# fanmon.net
KiCad netlist of a schematic drawn in EAGLE
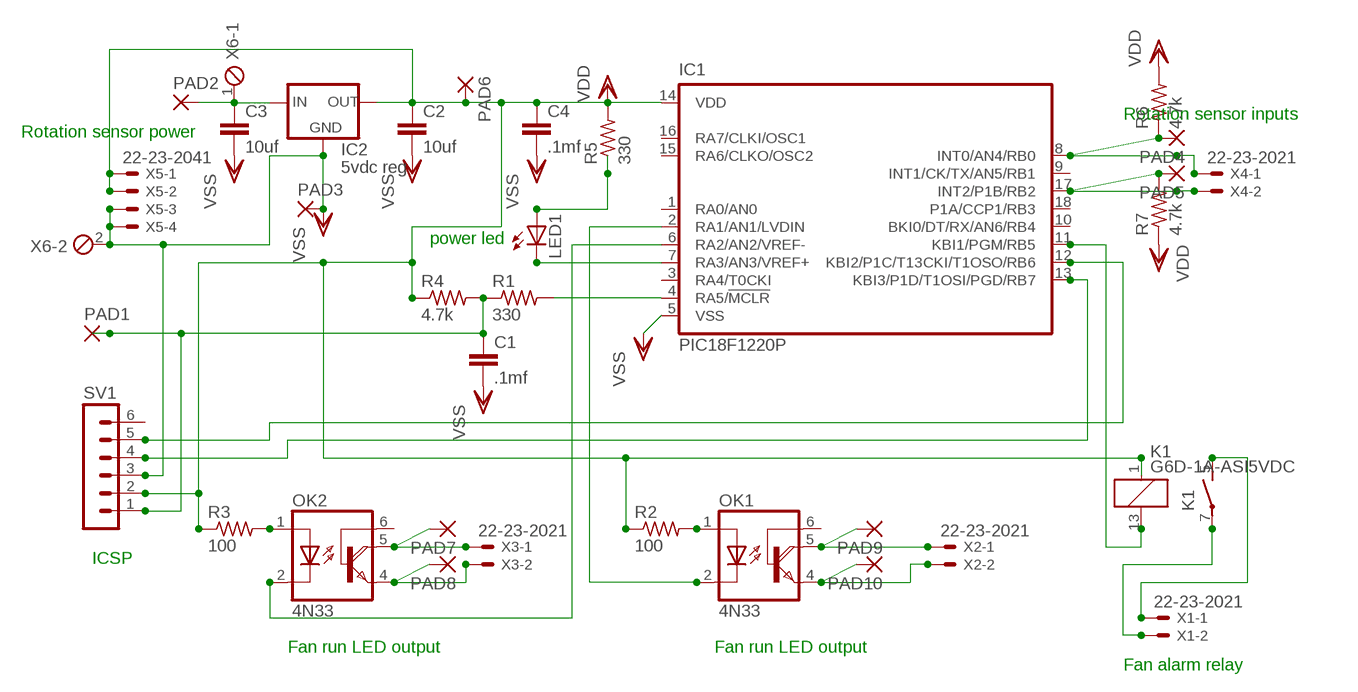
[diagram p0: schematic, sheet 1]

(export (version "E")
  (design (tool "Eeschema 10.0.6"))
  (components
    (comp (ref "C1")
      (value ".1mf")
      (footprint "eagle-import:C5B2.5")
      (libsource (lib "eagle-import") (part "C5/2.5"))
    )
    (comp (ref "C2")
      (value "10uf")
      (footprint "eagle-import:C5B2.5")
      (libsource (lib "eagle-import") (part "C5/2.5"))
    )
    (comp (ref "C3")
      (value "10uf")
      (footprint "eagle-import:C5B2.5")
      (libsource (lib "eagle-import") (part "C5/2.5"))
    )
    (comp (ref "C4")
      (value ".1mf")
      (footprint "eagle-import:C5B2.5")
      (libsource (lib "eagle-import") (part "C5/2.5"))
    )
    (comp (ref "IC1")
      (value "PIC18F1220P")
      (footprint "eagle-import:DIL18")
      (fields (field (name "MF") "MICROCHIP") (field (name "MPN") "PIC18F1220-I/P"))
      (libsource (lib "eagle-import") (part "PIC18F120P2"))
    )
    (comp (ref "IC2")
      (value "5vdc reg")
      (footprint "eagle-import:78XXL")
      (libsource (lib "eagle-import") (part "78XXL"))
    )
    (comp (ref "K1")
      (value "G6D-1A-ASI5VDC")
      (footprint "eagle-import:G6D")
      (libsource (lib "eagle-import") (part "G6D?-1A-ASI5VDC"))
    )
    (comp (ref "LED1")
      (value "LED5MM")
      (footprint "eagle-import:LED5MM")
      (libsource (lib "eagle-import") (part "LED5MM"))
    )
    (comp (ref "OK1")
      (value "4N33")
      (footprint "eagle-import:DIL06")
      (fields (field (name "MF") "VISHAY/TELEFUNKEN"))
      (libsource (lib "eagle-import") (part "4N33"))
    )
    (comp (ref "OK2")
      (value "4N33")
      (footprint "eagle-import:DIL06")
      (fields (field (name "MF") "VISHAY/TELEFUNKEN"))
      (libsource (lib "eagle-import") (part "4N33"))
    )
    (comp (ref "PAD1")
      (value "1,6/0,8")
      (footprint "eagle-import:1,6_0,8")
      (libsource (lib "eagle-import") (part "1,6/0,8"))
    )
    (comp (ref "PAD2")
      (value "1,6/0,8")
      (footprint "eagle-import:1,6_0,8")
      (libsource (lib "eagle-import") (part "1,6/0,8"))
    )
    (comp (ref "PAD3")
      (value "1,6/0,8")
      (footprint "eagle-import:1,6_0,8")
      (libsource (lib "eagle-import") (part "1,6/0,8"))
    )
    (comp (ref "PAD4")
      (value "1,6/0,8")
      (footprint "eagle-import:1,6_0,8")
      (libsource (lib "eagle-import") (part "1,6/0,8"))
    )
    (comp (ref "PAD5")
      (value "1,6/0,8")
      (footprint "eagle-import:1,6_0,8")
      (libsource (lib "eagle-import") (part "1,6/0,8"))
    )
    (comp (ref "PAD6")
      (value "1,6/0,8")
      (footprint "eagle-import:1,6_0,8")
      (libsource (lib "eagle-import") (part "1,6/0,8"))
    )
    (comp (ref "PAD7")
      (value "1,6/0,8")
      (footprint "eagle-import:1,6_0,8")
      (libsource (lib "eagle-import") (part "1,6/0,8"))
    )
    (comp (ref "PAD8")
      (value "1,6/0,8")
      (footprint "eagle-import:1,6_0,8")
      (libsource (lib "eagle-import") (part "1,6/0,8"))
    )
    (comp (ref "PAD9")
      (value "1,6/0,8")
      (footprint "eagle-import:1,6_0,8")
      (libsource (lib "eagle-import") (part "1,6/0,8"))
    )
    (comp (ref "PAD10")
      (value "1,6/0,8")
      (footprint "eagle-import:1,6_0,8")
      (libsource (lib "eagle-import") (part "1,6/0,8"))
    )
    (comp (ref "R1")
      (value "330")
      (footprint "eagle-import:0204V")
      (libsource (lib "eagle-import") (part "R-US_0204/2V"))
    )
    (comp (ref "R2")
      (value "100")
      (footprint "eagle-import:0204V")
      (libsource (lib "eagle-import") (part "R-US_0204/2V"))
    )
    (comp (ref "R3")
      (value "100")
      (footprint "eagle-import:0204V")
      (libsource (lib "eagle-import") (part "R-US_0204/2V"))
    )
    (comp (ref "R4")
      (value "4.7k")
      (footprint "eagle-import:0204V")
      (libsource (lib "eagle-import") (part "R-US_0204/2V"))
    )
    (comp (ref "R5")
      (value "330")
      (footprint "eagle-import:0204V")
      (libsource (lib "eagle-import") (part "R-US_0204/2V"))
    )
    (comp (ref "R6")
      (value "4.7k")
      (footprint "eagle-import:0204V")
      (libsource (lib "eagle-import") (part "R-US_0204/2V"))
    )
    (comp (ref "R7")
      (value "4.7k")
      (footprint "eagle-import:0204V")
      (libsource (lib "eagle-import") (part "R-US_0204/2V"))
    )
    (comp (ref "SV1")
      (value "MA06-1")
      (footprint "eagle-import:MA06-1")
      (libsource (lib "eagle-import") (part "MA06-1"))
    )
    (comp (ref "X1")
      (value "22-23-2021")
      (footprint "eagle-import:22-23-2021")
      (fields (field (name "MF") "MOLEX"))
      (libsource (lib "eagle-import") (part "22-23-2021"))
    )
    (comp (ref "X2")
      (value "22-23-2021")
      (footprint "eagle-import:22-23-2021")
      (fields (field (name "MF") "MOLEX"))
      (libsource (lib "eagle-import") (part "22-23-2021"))
    )
    (comp (ref "X3")
      (value "22-23-2021")
      (footprint "eagle-import:22-23-2021")
      (fields (field (name "MF") "MOLEX"))
      (libsource (lib "eagle-import") (part "22-23-2021"))
    )
    (comp (ref "X4")
      (value "22-23-2021")
      (footprint "eagle-import:22-23-2021")
      (fields (field (name "MF") "MOLEX"))
      (libsource (lib "eagle-import") (part "22-23-2021"))
    )
    (comp (ref "X5")
      (value "22-23-2041")
      (footprint "eagle-import:22-23-2041")
      (fields (field (name "MF") "MOLEX"))
      (libsource (lib "eagle-import") (part "22-23-2041"))
    )
    (comp (ref "X6")
      (value "MPT2")
      (footprint "eagle-import:2POL254")
      (libsource (lib "eagle-import") (part "MPT2"))
    )
  )
  (nets
    (net (code "1") (name "Net-(IC1-INT0{slash}AN4{slash}RB0)") (class "Default")
      (node (ref "IC1") (pin "8") (pinfunction "INT0/AN4/RB0_8") (pintype "bidirectional"))
      (node (ref "PAD4") (pin "1") (pinfunction "P_1") (pintype "passive"))
      (node (ref "R6") (pin "1") (pinfunction "1_1") (pintype "passive"))
      (node (ref "X4") (pin "1") (pinfunction "S_1") (pintype "passive"))
    )
    (net (code "2") (name "Net-(IC1-INT2{slash}P1B{slash}RB2)") (class "Default")
      (node (ref "IC1") (pin "17") (pinfunction "INT2/P1B/RB2_17") (pintype "bidirectional"))
      (node (ref "PAD5") (pin "1") (pinfunction "P_1") (pintype "passive"))
      (node (ref "R7") (pin "2") (pinfunction "2_2") (pintype "passive"))
      (node (ref "X4") (pin "2") (pinfunction "S_2") (pintype "passive"))
    )
    (net (code "3") (name "Net-(IC1-KBI1{slash}PGM{slash}RB5)") (class "Default")
      (node (ref "IC1") (pin "11") (pinfunction "KBI1/PGM/RB5_11") (pintype "bidirectional"))
      (node (ref "K1") (pin "13") (pinfunction "2_13") (pintype "passive"))
    )
    (net (code "4") (name "Net-(IC1-KBI2{slash}P1C{slash}T13CKI{slash}T1OSO{slash}RB6)") (class "Default")
      (node (ref "IC1") (pin "12") (pinfunction "KBI2/P1C/T13CKI/T1OSO/RB6_12") (pintype "bidirectional"))
      (node (ref "SV1") (pin "5") (pinfunction "5_5") (pintype "passive"))
    )
    (net (code "5") (name "Net-(IC1-KBI3{slash}P1D{slash}T1OSI{slash}PGD{slash}RB7)") (class "Default")
      (node (ref "IC1") (pin "13") (pinfunction "KBI3/P1D/T1OSI/PGD/RB7_13") (pintype "bidirectional"))
      (node (ref "SV1") (pin "4") (pinfunction "4_4") (pintype "passive"))
    )
    (net (code "6") (name "Net-(IC1-RA1{slash}AN1{slash}LVDIN)") (class "Default")
      (node (ref "IC1") (pin "2") (pinfunction "RA1/AN1/LVDIN_2") (pintype "bidirectional"))
      (node (ref "OK1") (pin "2") (pinfunction "C_2") (pintype "passive"))
    )
    (net (code "7") (name "Net-(IC1-RA2{slash}AN2{slash}VREF-)") (class "Default")
      (node (ref "IC1") (pin "6") (pinfunction "RA2/AN2/VREF-_6") (pintype "bidirectional"))
      (node (ref "OK2") (pin "2") (pinfunction "C_2") (pintype "passive"))
    )
    (net (code "8") (name "Net-(IC1-RA3{slash}AN3{slash}VREF+)") (class "Default")
      (node (ref "IC1") (pin "7") (pinfunction "RA3/AN3/VREF+_7") (pintype "bidirectional"))
      (node (ref "LED1") (pin "K") (pinfunction "C_K") (pintype "passive"))
    )
    (net (code "9") (name "Net-(IC1-RA5{slash}~{MCLR})") (class "Default")
      (node (ref "IC1") (pin "4") (pinfunction "RA5/~{MCLR}_4") (pintype "input"))
      (node (ref "R1") (pin "2") (pinfunction "2_2") (pintype "passive"))
    )
    (net (code "10") (name "Net-(K1B-P)") (class "Default")
      (node (ref "K1") (pin "7") (pinfunction "P_7") (pintype "passive"))
      (node (ref "X1") (pin "2") (pinfunction "S_2") (pintype "passive"))
    )
    (net (code "11") (name "Net-(K1B-S)") (class "Default")
      (node (ref "K1") (pin "5") (pinfunction "S_5") (pintype "passive"))
      (node (ref "X1") (pin "1") (pinfunction "S_1") (pintype "passive"))
    )
    (net (code "12") (name "Net-(LED1-PadA)") (class "Default")
      (node (ref "LED1") (pin "A") (pinfunction "A_A") (pintype "passive"))
      (node (ref "R5") (pin "1") (pinfunction "1_1") (pintype "passive"))
    )
    (net (code "13") (name "Net-(OK1-A)") (class "Default")
      (node (ref "OK1") (pin "1") (pinfunction "A_1") (pintype "passive"))
      (node (ref "R2") (pin "2") (pinfunction "2_2") (pintype "passive"))
    )
    (net (code "14") (name "Net-(OK1-COL)") (class "Default")
      (node (ref "OK1") (pin "5") (pinfunction "COL_5") (pintype "passive"))
      (node (ref "PAD9") (pin "1") (pinfunction "P_1") (pintype "passive"))
      (node (ref "X2") (pin "1") (pinfunction "S_1") (pintype "passive"))
    )
    (net (code "15") (name "Net-(OK1-E)") (class "Default")
      (node (ref "OK1") (pin "4") (pinfunction "E_4") (pintype "passive"))
      (node (ref "PAD10") (pin "1") (pinfunction "P_1") (pintype "passive"))
      (node (ref "X2") (pin "2") (pinfunction "S_2") (pintype "passive"))
    )
    (net (code "16") (name "Net-(OK2-A)") (class "Default")
      (node (ref "OK2") (pin "1") (pinfunction "A_1") (pintype "passive"))
      (node (ref "R3") (pin "2") (pinfunction "2_2") (pintype "passive"))
    )
    (net (code "17") (name "Net-(OK2-COL)") (class "Default")
      (node (ref "OK2") (pin "5") (pinfunction "COL_5") (pintype "passive"))
      (node (ref "PAD7") (pin "1") (pinfunction "P_1") (pintype "passive"))
      (node (ref "X3") (pin "1") (pinfunction "S_1") (pintype "passive"))
    )
    (net (code "18") (name "Net-(OK2-E)") (class "Default")
      (node (ref "OK2") (pin "4") (pinfunction "E_4") (pintype "passive"))
      (node (ref "PAD8") (pin "1") (pinfunction "P_1") (pintype "passive"))
      (node (ref "X3") (pin "2") (pinfunction "S_2") (pintype "passive"))
    )
    (net (code "19") (name "Net-(PAD1-P)") (class "Default")
      (node (ref "C1") (pin "1") (pinfunction "1_1") (pintype "passive"))
      (node (ref "PAD1") (pin "1") (pinfunction "P_1") (pintype "passive"))
      (node (ref "R1") (pin "1") (pinfunction "1_1") (pintype "passive"))
      (node (ref "R4") (pin "2") (pinfunction "2_2") (pintype "passive"))
      (node (ref "SV1") (pin "1") (pinfunction "1_1") (pintype "passive"))
    )
    (net (code "20") (name "Net-(PAD2-P)") (class "Default")
      (node (ref "C3") (pin "1") (pinfunction "1_1") (pintype "passive"))
      (node (ref "IC2") (pin "IN") (pinfunction "IN_IN") (pintype "input"))
      (node (ref "PAD2") (pin "1") (pinfunction "P_1") (pintype "passive"))
      (node (ref "X6") (pin "1") (pinfunction "1_1") (pintype "passive"))
    )
    (net (code "21") (name "VDD") (class "Default")
      (node (ref "C2") (pin "1") (pinfunction "1_1") (pintype "passive"))
      (node (ref "C4") (pin "1") (pinfunction "1_1") (pintype "passive"))
      (node (ref "IC1") (pin "14") (pinfunction "VDD_14") (pintype "power_in"))
      (node (ref "IC2") (pin "OUT") (pinfunction "OUT_OUT") (pintype "passive"))
      (node (ref "K1") (pin "1") (pinfunction "1_1") (pintype "passive"))
      (node (ref "PAD6") (pin "1") (pinfunction "P_1") (pintype "passive"))
      (node (ref "R2") (pin "1") (pinfunction "1_1") (pintype "passive"))
      (node (ref "R3") (pin "1") (pinfunction "1_1") (pintype "passive"))
      (node (ref "R4") (pin "1") (pinfunction "1_1") (pintype "passive"))
      (node (ref "R5") (pin "2") (pinfunction "2_2") (pintype "passive"))
      (node (ref "R6") (pin "2") (pinfunction "2_2") (pintype "passive"))
      (node (ref "R7") (pin "1") (pinfunction "1_1") (pintype "passive"))
      (node (ref "SV1") (pin "2") (pinfunction "2_2") (pintype "passive"))
      (node (ref "X5") (pin "1") (pinfunction "S_1") (pintype "passive"))
      (node (ref "X5") (pin "2") (pinfunction "S_2") (pintype "passive"))
    )
    (net (code "22") (name "VSS") (class "Default")
      (node (ref "C1") (pin "2") (pinfunction "2_2") (pintype "passive"))
      (node (ref "C2") (pin "2") (pinfunction "2_2") (pintype "passive"))
      (node (ref "C3") (pin "2") (pinfunction "2_2") (pintype "passive"))
      (node (ref "C4") (pin "2") (pinfunction "2_2") (pintype "passive"))
      (node (ref "IC1") (pin "5") (pinfunction "VSS_5") (pintype "power_in"))
      (node (ref "IC2") (pin "GND") (pinfunction "GND_GND") (pintype "input"))
      (node (ref "PAD3") (pin "1") (pinfunction "P_1") (pintype "passive"))
      (node (ref "SV1") (pin "3") (pinfunction "3_3") (pintype "passive"))
      (node (ref "X5") (pin "3") (pinfunction "S_3") (pintype "passive"))
      (node (ref "X5") (pin "4") (pinfunction "S_4") (pintype "passive"))
      (node (ref "X6") (pin "2") (pinfunction "1_2") (pintype "passive"))
    )
    (net (code "23") (name "unconnected-(IC1-BKI0{slash}DT{slash}RX{slash}AN6{slash}RB4-Pad10)") (class "Default")
      (node (ref "IC1") (pin "10") (pinfunction "BKI0/DT/RX/AN6/RB4_10") (pintype "bidirectional"))
    )
    (net (code "24") (name "unconnected-(IC1-INT1{slash}CK{slash}TX{slash}AN5{slash}RB1-Pad9)") (class "Default")
      (node (ref "IC1") (pin "9") (pinfunction "INT1/CK/TX/AN5/RB1_9") (pintype "bidirectional"))
    )
    (net (code "25") (name "unconnected-(IC1-P1A{slash}CCP1{slash}RB3-Pad18)") (class "Default")
      (node (ref "IC1") (pin "18") (pinfunction "P1A/CCP1/RB3_18") (pintype "bidirectional"))
    )
    (net (code "26") (name "unconnected-(IC1-RA0{slash}AN0-Pad1)") (class "Default")
      (node (ref "IC1") (pin "1") (pinfunction "RA0/AN0_1") (pintype "bidirectional"))
    )
    (net (code "27") (name "unconnected-(IC1-RA4{slash}T0CKI-Pad3)") (class "Default")
      (node (ref "IC1") (pin "3") (pinfunction "RA4/T0CKI_3") (pintype "bidirectional"))
    )
    (net (code "28") (name "unconnected-(IC1-RA6{slash}CLKO{slash}OSC2-Pad15)") (class "Default")
      (node (ref "IC1") (pin "15") (pinfunction "RA6/CLKO/OSC2_15") (pintype "bidirectional"))
    )
    (net (code "29") (name "unconnected-(IC1-RA7{slash}CLKI{slash}OSC1-Pad16)") (class "Default")
      (node (ref "IC1") (pin "16") (pinfunction "RA7/CLKI/OSC1_16") (pintype "bidirectional"))
    )
    (net (code "30") (name "unconnected-(OK1-B-Pad6)") (class "Default")
      (node (ref "OK1") (pin "6") (pinfunction "B_6") (pintype "passive"))
    )
    (net (code "31") (name "unconnected-(OK2-B-Pad6)") (class "Default")
      (node (ref "OK2") (pin "6") (pinfunction "B_6") (pintype "passive"))
    )
    (net (code "32") (name "unconnected-(SV1-Pad6)") (class "Default")
      (node (ref "SV1") (pin "6") (pinfunction "6_6") (pintype "passive"))
    )
  )
)
